# 150306_AriloTX_REV3_1_0_868MHZ_CORRECT_T.net
KiCad netlist of a schematic drawn in EAGLE
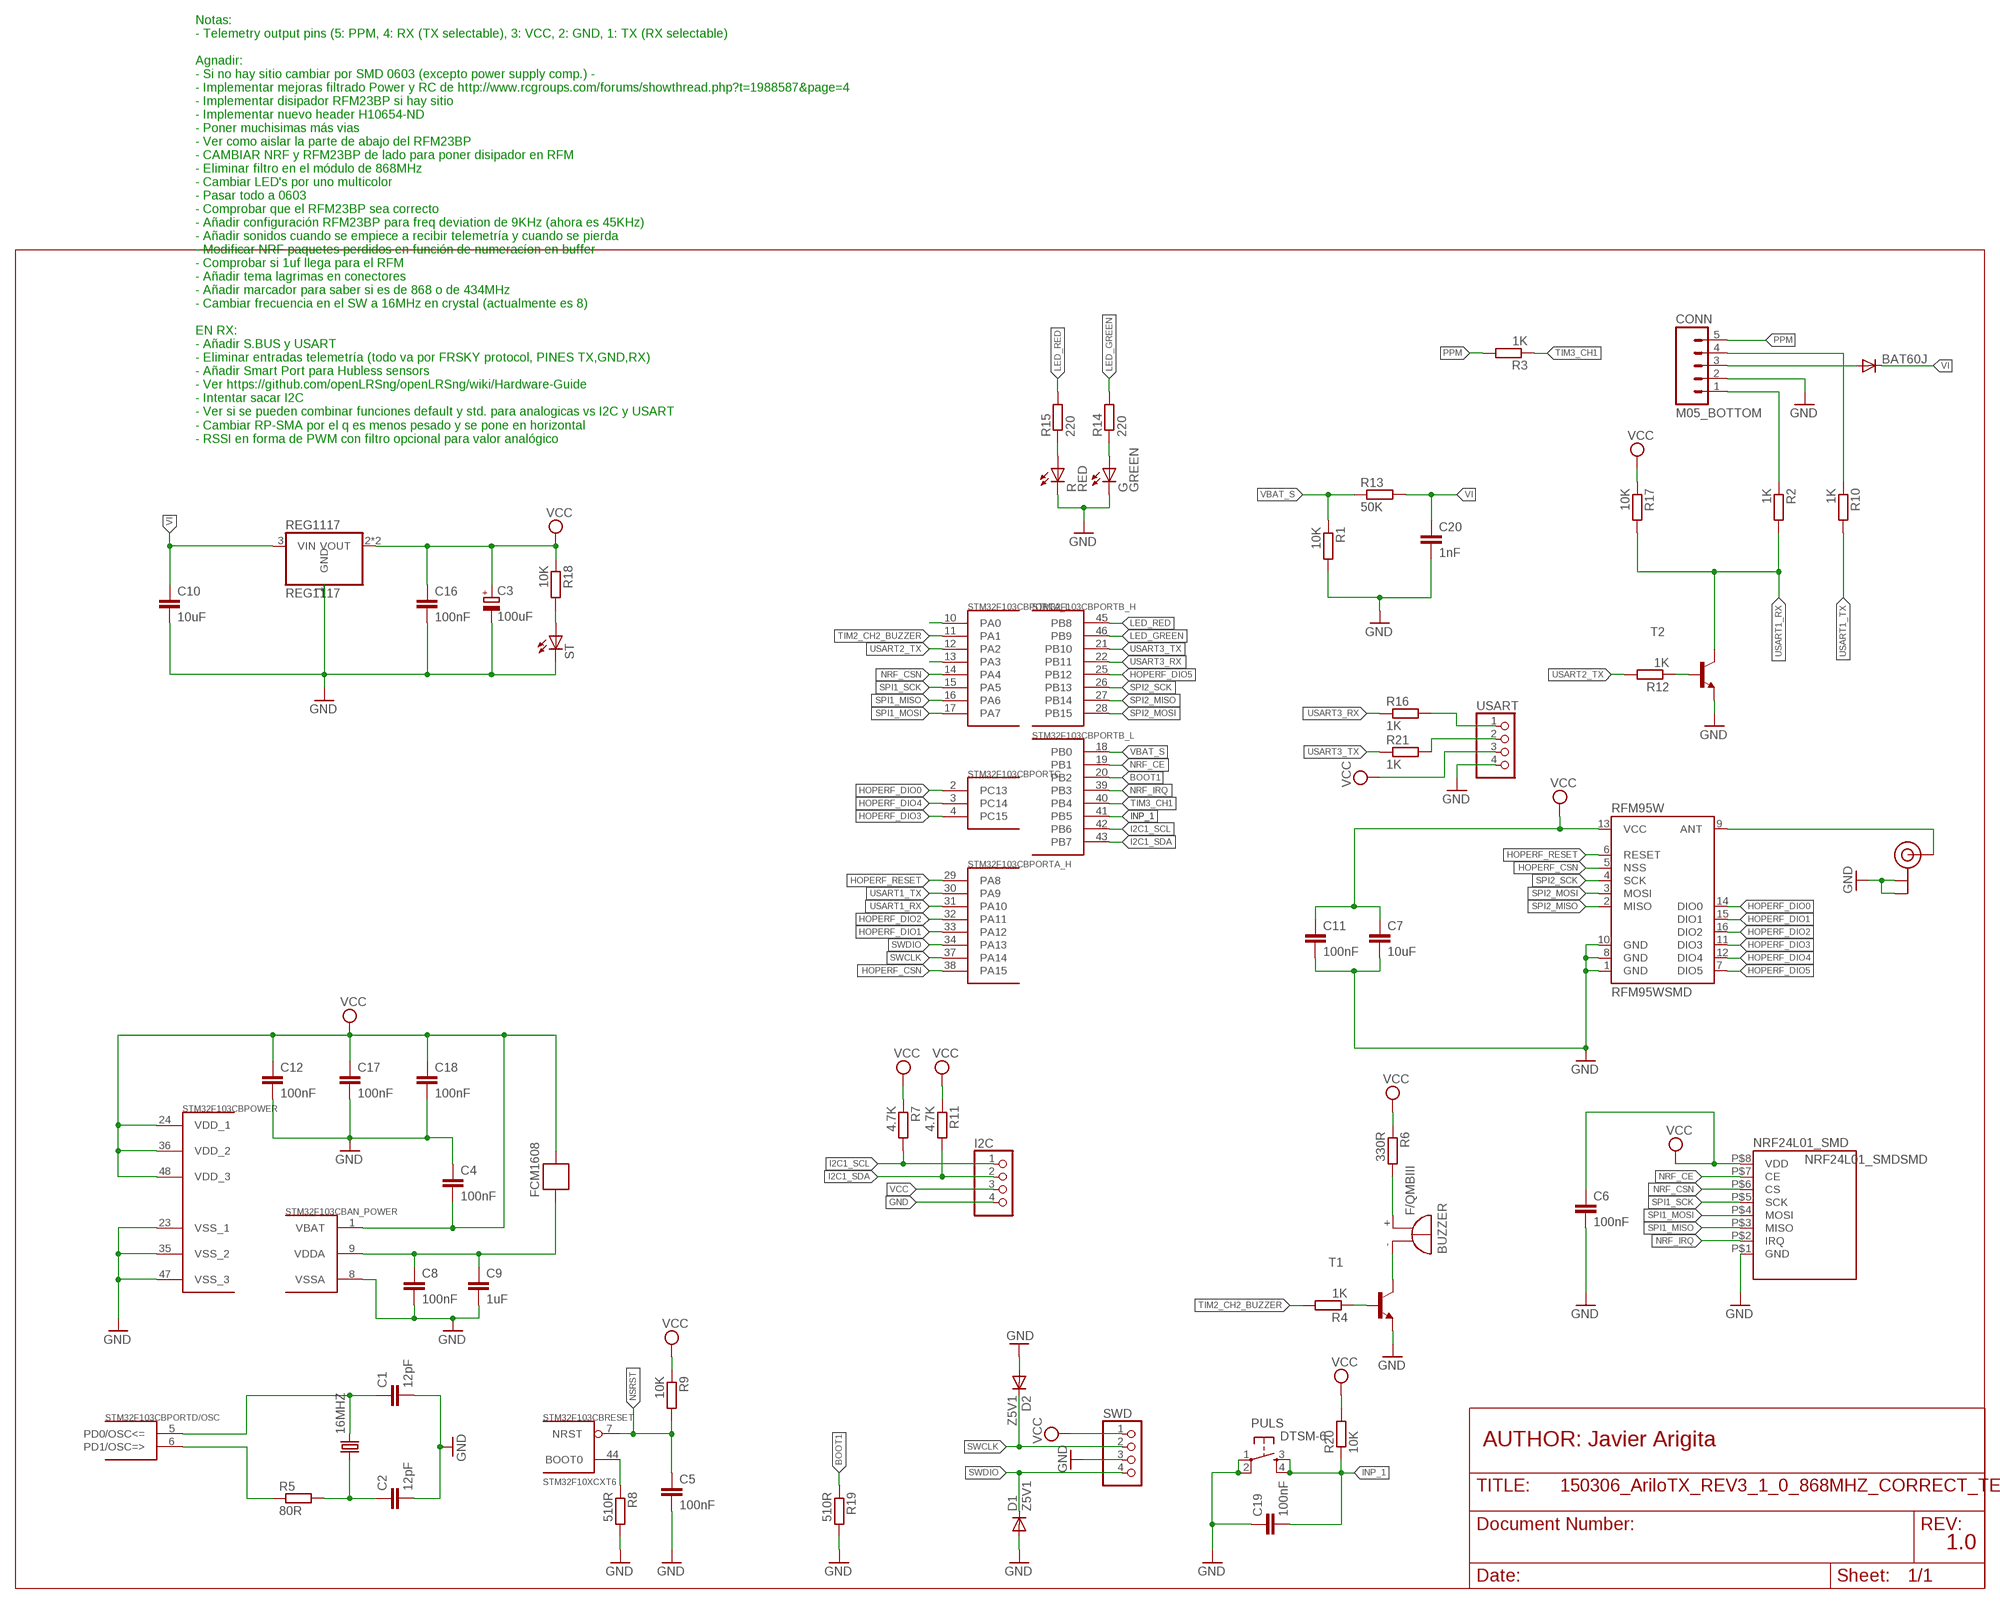
[diagram p0: schematic, sheet 1]

(export (version "E")
  (design (tool "Eeschema 10.0.6"))
  (components
    (comp (ref "16MHZ")
      (value "CRYSTAL5X3")
      (footprint "eagle-import:CRYSTAL-SMD-5X3")
      (libsource (lib "eagle-import") (part "CRYSTAL5X3"))
    )
    (comp (ref "BAT60J")
      (value "DIODE-SOD323-R")
      (footprint "eagle-import:SOD323-R")
      (libsource (lib "eagle-import") (part "DIODE-SOD323-R"))
    )
    (comp (ref "BUZZER")
      (value "F/QMBIII")
      (footprint "eagle-import:F_QMBIII")
      (libsource (lib "eagle-import") (part "F/QMBIII"))
    )
    (comp (ref "C1")
      (value "12pF")
      (footprint "eagle-import:C0603")
      (libsource (lib "eagle-import") (part "C-EUC0603"))
    )
    (comp (ref "C2")
      (value "12pF")
      (footprint "eagle-import:C0603")
      (libsource (lib "eagle-import") (part "C-EUC0603"))
    )
    (comp (ref "C3")
      (value "100uF")
      (footprint "eagle-import:SMC_B")
      (libsource (lib "eagle-import") (part "CPOL-EUSMCB"))
    )
    (comp (ref "C4")
      (value "100nF")
      (footprint "eagle-import:C0603")
      (libsource (lib "eagle-import") (part "C-EUC0603"))
    )
    (comp (ref "C5")
      (value "100nF")
      (footprint "eagle-import:C0603")
      (libsource (lib "eagle-import") (part "C-EUC0603"))
    )
    (comp (ref "C6")
      (value "100nF")
      (footprint "eagle-import:C0603")
      (libsource (lib "eagle-import") (part "C-EUC0603"))
    )
    (comp (ref "C7")
      (value "10uF")
      (footprint "eagle-import:C3216")
      (libsource (lib "eagle-import") (part "resistor_C-EUC3216"))
    )
    (comp (ref "C8")
      (value "100nF")
      (footprint "eagle-import:C0603")
      (libsource (lib "eagle-import") (part "C-EUC0603"))
    )
    (comp (ref "C9")
      (value "1uF")
      (footprint "eagle-import:C0603")
      (libsource (lib "eagle-import") (part "C-EUC0603"))
    )
    (comp (ref "C10")
      (value "10uF")
      (footprint "eagle-import:C3216")
      (libsource (lib "eagle-import") (part "resistor_C-EUC3216"))
    )
    (comp (ref "C11")
      (value "100nF")
      (footprint "eagle-import:C0603")
      (libsource (lib "eagle-import") (part "C-EUC0603"))
    )
    (comp (ref "C12")
      (value "100nF")
      (footprint "eagle-import:C0603")
      (libsource (lib "eagle-import") (part "C-EUC0603"))
    )
    (comp (ref "C16")
      (value "100nF")
      (footprint "eagle-import:C0603")
      (libsource (lib "eagle-import") (part "C-EUC0603"))
    )
    (comp (ref "C17")
      (value "100nF")
      (footprint "eagle-import:C0603")
      (libsource (lib "eagle-import") (part "C-EUC0603"))
    )
    (comp (ref "C18")
      (value "100nF")
      (footprint "eagle-import:C0603")
      (libsource (lib "eagle-import") (part "C-EUC0603"))
    )
    (comp (ref "C19")
      (value "100nF")
      (footprint "eagle-import:C0603")
      (libsource (lib "eagle-import") (part "C-EUC0603"))
    )
    (comp (ref "C20")
      (value "1nF")
      (footprint "eagle-import:C0603")
      (libsource (lib "eagle-import") (part "C-EUC0603"))
    )
    (comp (ref "CONN")
      (value "M05_BOTTOM")
      (footprint "eagle-import:M05_BOTTOM")
      (libsource (lib "eagle-import") (part "M05_BOTTOM"))
    )
    (comp (ref "D1")
      (value "Z5V1")
      (footprint "eagle-import:SOD323-R")
      (libsource (lib "eagle-import") (part "DIODE-SOD323-R"))
    )
    (comp (ref "D2")
      (value "Z5V1")
      (footprint "eagle-import:SOD323-R")
      (libsource (lib "eagle-import") (part "DIODE-SOD323-R"))
    )
    (comp (ref "FCM1608")
      (value "FERRITE-BEAD")
      (footprint "eagle-import:R0603")
      (libsource (lib "eagle-import") (part "FERRITE-BEAD"))
    )
    (comp (ref "G")
      (value "GREEN")
      (footprint "eagle-import:CHIP-LED0603")
      (libsource (lib "eagle-import") (part "LEDCHIP-LED0603"))
    )
    (comp (ref "I2C")
      (value "PINHD-1X4")
      (footprint "eagle-import:1X04")
      (libsource (lib "eagle-import") (part "PINHD-1X4"))
    )
    (comp (ref "NRF24L01_SMD")
      (value "NRF24L01_SMDSMD")
      (footprint "eagle-import:NRF24L01_SMD")
      (libsource (lib "eagle-import") (part "NRF24L01_SMDSMD"))
    )
    (comp (ref "PULS")
      (value "DTSM-6")
      (footprint "eagle-import:DTSM-6")
      (libsource (lib "eagle-import") (part "DTSM-6"))
    )
    (comp (ref "R")
      (value "RED")
      (footprint "eagle-import:CHIP-LED0603")
      (libsource (lib "eagle-import") (part "LEDCHIP-LED0603"))
    )
    (comp (ref "R1")
      (value "10K")
      (footprint "eagle-import:R0603")
      (libsource (lib "eagle-import") (part "R-EU_R0603"))
    )
    (comp (ref "R2")
      (value "1K")
      (footprint "eagle-import:R0603")
      (libsource (lib "eagle-import") (part "R-EU_R0603"))
    )
    (comp (ref "R3")
      (value "1K")
      (footprint "eagle-import:R0603")
      (libsource (lib "eagle-import") (part "R-EU_R0603"))
    )
    (comp (ref "R4")
      (value "1K")
      (footprint "eagle-import:R0603")
      (libsource (lib "eagle-import") (part "R-EU_R0603"))
    )
    (comp (ref "R5")
      (value "80R")
      (footprint "eagle-import:R0603")
      (libsource (lib "eagle-import") (part "R-EU_R0603"))
    )
    (comp (ref "R6")
      (value "330R")
      (footprint "eagle-import:R0603")
      (libsource (lib "eagle-import") (part "R-EU_R0603"))
    )
    (comp (ref "R7")
      (value "4.7K")
      (footprint "eagle-import:R0603")
      (libsource (lib "eagle-import") (part "R-EU_R0603"))
    )
    (comp (ref "R8")
      (value "510R")
      (footprint "eagle-import:R0603")
      (libsource (lib "eagle-import") (part "R-EU_R0603"))
    )
    (comp (ref "R9")
      (value "10K")
      (footprint "eagle-import:R0603")
      (libsource (lib "eagle-import") (part "R-EU_R0603"))
    )
    (comp (ref "R10")
      (value "1K")
      (footprint "eagle-import:R0603")
      (libsource (lib "eagle-import") (part "R-EU_R0603"))
    )
    (comp (ref "R11")
      (value "4.7K")
      (footprint "eagle-import:R0603")
      (libsource (lib "eagle-import") (part "R-EU_R0603"))
    )
    (comp (ref "R12")
      (value "1K")
      (footprint "eagle-import:R0603")
      (libsource (lib "eagle-import") (part "R-EU_R0603"))
    )
    (comp (ref "R13")
      (value "50K")
      (footprint "eagle-import:R0603")
      (libsource (lib "eagle-import") (part "R-EU_R0603"))
    )
    (comp (ref "R14")
      (value "220")
      (footprint "eagle-import:R0603")
      (libsource (lib "eagle-import") (part "R-EU_R0603"))
    )
    (comp (ref "R15")
      (value "220")
      (footprint "eagle-import:R0603")
      (libsource (lib "eagle-import") (part "R-EU_R0603"))
    )
    (comp (ref "R16")
      (value "1K")
      (footprint "eagle-import:R0603")
      (libsource (lib "eagle-import") (part "R-EU_R0603"))
    )
    (comp (ref "R17")
      (value "10K")
      (footprint "eagle-import:R0603")
      (libsource (lib "eagle-import") (part "R-EU_R0603"))
    )
    (comp (ref "R18")
      (value "10K")
      (footprint "eagle-import:R0603")
      (libsource (lib "eagle-import") (part "R-EU_R0603"))
    )
    (comp (ref "R19")
      (value "510R")
      (footprint "eagle-import:R0603")
      (libsource (lib "eagle-import") (part "R-EU_R0603"))
    )
    (comp (ref "R20")
      (value "10K")
      (footprint "eagle-import:R0603")
      (libsource (lib "eagle-import") (part "R-EU_R0603"))
    )
    (comp (ref "R21")
      (value "1K")
      (footprint "eagle-import:R0603")
      (libsource (lib "eagle-import") (part "R-EU_R0603"))
    )
    (comp (ref "REG1117")
      (value "REG1117")
      (footprint "eagle-import:SOT223")
      (libsource (lib "eagle-import") (part "REG1117"))
    )
    (comp (ref "RFM95W")
      (value "RFM95WSMD")
      (footprint "eagle-import:MISIEK_RFM95W_SMD")
      (libsource (lib "eagle-import") (part "MISIEK_RFM95WSMD"))
    )
    (comp (ref "ST")
      (value "LEDCHIP-LED0603")
      (footprint "eagle-import:CHIP-LED0603")
      (libsource (lib "eagle-import") (part "LEDCHIP-LED0603"))
    )
    (comp (ref "STM32F103CB")
      (value "STM32F10XCXT6")
      (footprint "eagle-import:TQFP48")
      (libsource (lib "eagle-import") (part "STM32F10XCXT6"))
    )
    (comp (ref "SWD")
      (value "PINHD-1X4")
      (footprint "eagle-import:1X04")
      (libsource (lib "eagle-import") (part "PINHD-1X4"))
    )
    (comp (ref "T1")
      (value "BC848-NPN-SOT23-BEC")
      (footprint "eagle-import:SOT23-BEC")
      (libsource (lib "eagle-import") (part "-NPN-SOT23-BECBC848"))
    )
    (comp (ref "T2")
      (value "BC848-NPN-SOT23-BEC")
      (footprint "eagle-import:SOT23-BEC")
      (libsource (lib "eagle-import") (part "-NPN-SOT23-BECBC848"))
    )
    (comp (ref "U.FL")
      (value "U.FL")
      (footprint "eagle-import:U.FL")
      (libsource (lib "eagle-import") (part "U.FL"))
    )
    (comp (ref "USART")
      (value "PINHD-1X4")
      (footprint "eagle-import:1X04")
      (libsource (lib "eagle-import") (part "PINHD-1X4"))
    )
  )
  (nets
    (net (code "1") (name "BOOT1") (class "Default")
      (node (ref "R19") (pin "1") (pinfunction "1_1") (pintype "passive"))
      (node (ref "STM32F103CB") (pin "20") (pinfunction "PB2_20") (pintype "bidirectional"))
    )
    (net (code "2") (name "GND") (class "Default")
      (node (ref "C1") (pin "2") (pinfunction "2_2") (pintype "passive"))
      (node (ref "C10") (pin "2") (pinfunction "2_2") (pintype "passive"))
      (node (ref "C11") (pin "2") (pinfunction "2_2") (pintype "passive"))
      (node (ref "C12") (pin "2") (pinfunction "2_2") (pintype "passive"))
      (node (ref "C16") (pin "2") (pinfunction "2_2") (pintype "passive"))
      (node (ref "C17") (pin "2") (pinfunction "2_2") (pintype "passive"))
      (node (ref "C18") (pin "2") (pinfunction "2_2") (pintype "passive"))
      (node (ref "C19") (pin "1") (pinfunction "1_1") (pintype "passive"))
      (node (ref "C2") (pin "2") (pinfunction "2_2") (pintype "passive"))
      (node (ref "C20") (pin "2") (pinfunction "2_2") (pintype "passive"))
      (node (ref "C3") (pin "-") (pinfunction "-_-") (pintype "passive"))
      (node (ref "C4") (pin "1") (pinfunction "1_1") (pintype "passive"))
      (node (ref "C5") (pin "2") (pinfunction "2_2") (pintype "passive"))
      (node (ref "C6") (pin "2") (pinfunction "2_2") (pintype "passive"))
      (node (ref "C7") (pin "2") (pinfunction "2_2") (pintype "passive"))
      (node (ref "C8") (pin "2") (pinfunction "2_2") (pintype "passive"))
      (node (ref "C9") (pin "2") (pinfunction "2_2") (pintype "passive"))
      (node (ref "CONN") (pin "2") (pinfunction "2_2") (pintype "passive"))
      (node (ref "D1") (pin "A") (pinfunction "A_A") (pintype "passive"))
      (node (ref "D2") (pin "A") (pinfunction "A_A") (pintype "passive"))
      (node (ref "G") (pin "C") (pinfunction "C_C") (pintype "passive"))
      (node (ref "I2C") (pin "4") (pinfunction "4_4") (pintype "passive"))
      (node (ref "NRF24L01_SMD") (pin "P$1") (pinfunction "GND_P$1") (pintype "power_in"))
      (node (ref "PULS") (pin "1") (pinfunction "1_1") (pintype "passive"))
      (node (ref "PULS") (pin "2") (pinfunction "2_2") (pintype "passive"))
      (node (ref "R") (pin "C") (pinfunction "C_C") (pintype "passive"))
      (node (ref "R1") (pin "2") (pinfunction "2_2") (pintype "passive"))
      (node (ref "R19") (pin "2") (pinfunction "2_2") (pintype "passive"))
      (node (ref "R8") (pin "2") (pinfunction "2_2") (pintype "passive"))
      (node (ref "REG1117") (pin "1") (pinfunction "GND_1") (pintype "power_in"))
      (node (ref "RFM95W") (pin "1") (pinfunction "GND_1") (pintype "power_in"))
      (node (ref "RFM95W") (pin "10") (pinfunction "GND_10") (pintype "power_in"))
      (node (ref "RFM95W") (pin "8") (pinfunction "GND_8") (pintype "power_in"))
      (node (ref "ST") (pin "C") (pinfunction "C_C") (pintype "passive"))
      (node (ref "STM32F103CB") (pin "23") (pinfunction "VSS_1_23") (pintype "power_in"))
      (node (ref "STM32F103CB") (pin "35") (pinfunction "VSS_2_35") (pintype "power_in"))
      (node (ref "STM32F103CB") (pin "47") (pinfunction "VSS_3_47") (pintype "power_in"))
      (node (ref "STM32F103CB") (pin "8") (pinfunction "VSSA_8") (pintype "power_in"))
      (node (ref "SWD") (pin "3") (pinfunction "3_3") (pintype "passive"))
      (node (ref "T1") (pin "E") (pinfunction "E_E") (pintype "passive"))
      (node (ref "T2") (pin "E") (pinfunction "E_E") (pintype "passive"))
      (node (ref "U.FL") (pin "P$1") (pinfunction "GND_P$1") (pintype "bidirectional"))
      (node (ref "U.FL") (pin "P$2") (pinfunction "GND_P$2") (pintype "bidirectional"))
      (node (ref "USART") (pin "4") (pinfunction "4_4") (pintype "passive"))
    )
    (net (code "3") (name "HOPERF_CSN") (class "Default")
      (node (ref "RFM95W") (pin "5") (pinfunction "NSS_5") (pintype "input"))
      (node (ref "STM32F103CB") (pin "38") (pinfunction "PA15_38") (pintype "bidirectional"))
    )
    (net (code "4") (name "HOPERF_DIO0") (class "Default")
      (node (ref "RFM95W") (pin "14") (pinfunction "DIO0_14") (pintype "input"))
      (node (ref "STM32F103CB") (pin "2") (pinfunction "PC13_2") (pintype "bidirectional"))
    )
    (net (code "5") (name "HOPERF_DIO1") (class "Default")
      (node (ref "RFM95W") (pin "15") (pinfunction "DIO1_15") (pintype "input"))
      (node (ref "STM32F103CB") (pin "33") (pinfunction "PA12_33") (pintype "bidirectional"))
    )
    (net (code "6") (name "HOPERF_DIO2") (class "Default")
      (node (ref "RFM95W") (pin "16") (pinfunction "DIO2_16") (pintype "input"))
      (node (ref "STM32F103CB") (pin "32") (pinfunction "PA11_32") (pintype "bidirectional"))
    )
    (net (code "7") (name "HOPERF_DIO3") (class "Default")
      (node (ref "RFM95W") (pin "11") (pinfunction "DIO3_11") (pintype "bidirectional"))
      (node (ref "STM32F103CB") (pin "4") (pinfunction "PC15_4") (pintype "bidirectional"))
    )
    (net (code "8") (name "HOPERF_DIO4") (class "Default")
      (node (ref "RFM95W") (pin "12") (pinfunction "DIO4_12") (pintype "bidirectional"))
      (node (ref "STM32F103CB") (pin "3") (pinfunction "PC14_3") (pintype "bidirectional"))
    )
    (net (code "9") (name "HOPERF_DIO5") (class "Default")
      (node (ref "RFM95W") (pin "7") (pinfunction "DIO5_7") (pintype "bidirectional"))
      (node (ref "STM32F103CB") (pin "25") (pinfunction "PB12_25") (pintype "bidirectional"))
    )
    (net (code "10") (name "HOPERF_RESET") (class "Default")
      (node (ref "RFM95W") (pin "6") (pinfunction "RESET_6") (pintype "output"))
      (node (ref "STM32F103CB") (pin "29") (pinfunction "PA8_29") (pintype "bidirectional"))
    )
    (net (code "11") (name "I2C1_SCL") (class "Default")
      (node (ref "I2C") (pin "1") (pinfunction "1_1") (pintype "passive"))
      (node (ref "R7") (pin "2") (pinfunction "2_2") (pintype "passive"))
      (node (ref "STM32F103CB") (pin "42") (pinfunction "PB6_42") (pintype "bidirectional"))
    )
    (net (code "12") (name "I2C1_SDA") (class "Default")
      (node (ref "I2C") (pin "2") (pinfunction "2_2") (pintype "passive"))
      (node (ref "R11") (pin "2") (pinfunction "2_2") (pintype "passive"))
      (node (ref "STM32F103CB") (pin "43") (pinfunction "PB7_43") (pintype "bidirectional"))
    )
    (net (code "13") (name "INP_1") (class "Default")
      (node (ref "C19") (pin "2") (pinfunction "2_2") (pintype "passive"))
      (node (ref "PULS") (pin "3") (pinfunction "3_3") (pintype "passive"))
      (node (ref "PULS") (pin "4") (pinfunction "4_4") (pintype "passive"))
      (node (ref "R20") (pin "1") (pinfunction "1_1") (pintype "passive"))
      (node (ref "STM32F103CB") (pin "41") (pinfunction "PB5_41") (pintype "bidirectional"))
    )
    (net (code "14") (name "LED_GREEN") (class "Default")
      (node (ref "R14") (pin "2") (pinfunction "2_2") (pintype "passive"))
      (node (ref "STM32F103CB") (pin "46") (pinfunction "PB9_46") (pintype "bidirectional"))
    )
    (net (code "15") (name "LED_RED") (class "Default")
      (node (ref "R15") (pin "2") (pinfunction "2_2") (pintype "passive"))
      (node (ref "STM32F103CB") (pin "45") (pinfunction "PB8_45") (pintype "bidirectional"))
    )
    (net (code "16") (name "NRF_CE") (class "Default")
      (node (ref "NRF24L01_SMD") (pin "P$7") (pinfunction "CE_P$7") (pintype "input"))
      (node (ref "STM32F103CB") (pin "19") (pinfunction "PB1_19") (pintype "bidirectional"))
    )
    (net (code "17") (name "NRF_CSN") (class "Default")
      (node (ref "NRF24L01_SMD") (pin "P$6") (pinfunction "CS_P$6") (pintype "input"))
      (node (ref "STM32F103CB") (pin "14") (pinfunction "PA4_14") (pintype "bidirectional"))
    )
    (net (code "18") (name "NRF_IRQ") (class "Default")
      (node (ref "NRF24L01_SMD") (pin "P$2") (pinfunction "IRQ_P$2") (pintype "output"))
      (node (ref "STM32F103CB") (pin "39") (pinfunction "PB3_39") (pintype "bidirectional"))
    )
    (net (code "19") (name "NSRST") (class "Default")
      (node (ref "C5") (pin "1") (pinfunction "1_1") (pintype "passive"))
      (node (ref "R9") (pin "2") (pinfunction "2_2") (pintype "passive"))
      (node (ref "STM32F103CB") (pin "7") (pinfunction "NRST_7") (pintype "input"))
    )
    (net (code "20") (name "Net-(16MHZ-2)") (class "Default")
      (node (ref "16MHZ") (pin "3") (pinfunction "2_3") (pintype "passive"))
      (node (ref "C1") (pin "1") (pinfunction "1_1") (pintype "passive"))
      (node (ref "STM32F103CB") (pin "5") (pinfunction "PD0/OSC<=_5") (pintype "bidirectional"))
    )
    (net (code "21") (name "Net-(16MHZ-Pad1)") (class "Default")
      (node (ref "16MHZ") (pin "1") (pinfunction "1_1") (pintype "passive"))
      (node (ref "C2") (pin "1") (pinfunction "1_1") (pintype "passive"))
      (node (ref "R5") (pin "2") (pinfunction "2_2") (pintype "passive"))
    )
    (net (code "22") (name "Net-(BAT60J-PadA)") (class "Default")
      (node (ref "BAT60J") (pin "A") (pinfunction "A_A") (pintype "passive"))
      (node (ref "CONN") (pin "3") (pinfunction "3_3") (pintype "passive"))
    )
    (net (code "23") (name "Net-(BUZZER-+)") (class "Default")
      (node (ref "BUZZER") (pin "-") (pinfunction "+_-") (pintype "passive"))
      (node (ref "T1") (pin "C") (pinfunction "C_C") (pintype "passive"))
    )
    (net (code "24") (name "Net-(BUZZER--)") (class "Default")
      (node (ref "BUZZER") (pin "+") (pinfunction "-_+") (pintype "passive"))
      (node (ref "R6") (pin "2") (pinfunction "2_2") (pintype "passive"))
    )
    (net (code "25") (name "Net-(CONN-Pad1)") (class "Default")
      (node (ref "CONN") (pin "1") (pinfunction "1_1") (pintype "passive"))
      (node (ref "R2") (pin "1") (pinfunction "1_1") (pintype "passive"))
    )
    (net (code "26") (name "Net-(CONN-Pad4)") (class "Default")
      (node (ref "CONN") (pin "4") (pinfunction "4_4") (pintype "passive"))
      (node (ref "R10") (pin "1") (pinfunction "1_1") (pintype "passive"))
    )
    (net (code "27") (name "Net-(FCM1608-P$2)") (class "Default")
      (node (ref "C8") (pin "1") (pinfunction "1_1") (pintype "passive"))
      (node (ref "C9") (pin "1") (pinfunction "1_1") (pintype "passive"))
      (node (ref "FCM1608") (pin "2") (pinfunction "P$2_2") (pintype "bidirectional"))
      (node (ref "STM32F103CB") (pin "9") (pinfunction "VDDA_9") (pintype "power_in"))
    )
    (net (code "28") (name "Net-(G-PadA)") (class "Default")
      (node (ref "G") (pin "A") (pinfunction "A_A") (pintype "passive"))
      (node (ref "R14") (pin "1") (pinfunction "1_1") (pintype "passive"))
    )
    (net (code "29") (name "Net-(R-PadA)") (class "Default")
      (node (ref "R") (pin "A") (pinfunction "A_A") (pintype "passive"))
      (node (ref "R15") (pin "1") (pinfunction "1_1") (pintype "passive"))
    )
    (net (code "30") (name "Net-(R4-Pad1)") (class "Default")
      (node (ref "R4") (pin "1") (pinfunction "1_1") (pintype "passive"))
      (node (ref "T1") (pin "B") (pinfunction "B_B") (pintype "passive"))
    )
    (net (code "31") (name "Net-(R12-Pad1)") (class "Default")
      (node (ref "R12") (pin "1") (pinfunction "1_1") (pintype "passive"))
      (node (ref "T2") (pin "B") (pinfunction "B_B") (pintype "passive"))
    )
    (net (code "32") (name "Net-(R16-Pad2)") (class "Default")
      (node (ref "R16") (pin "2") (pinfunction "2_2") (pintype "passive"))
      (node (ref "USART") (pin "1") (pinfunction "1_1") (pintype "passive"))
    )
    (net (code "33") (name "Net-(R18-Pad2)") (class "Default")
      (node (ref "R18") (pin "2") (pinfunction "2_2") (pintype "passive"))
      (node (ref "ST") (pin "A") (pinfunction "A_A") (pintype "passive"))
    )
    (net (code "34") (name "Net-(R21-Pad2)") (class "Default")
      (node (ref "R21") (pin "2") (pinfunction "2_2") (pintype "passive"))
      (node (ref "USART") (pin "2") (pinfunction "2_2") (pintype "passive"))
    )
    (net (code "35") (name "Net-(RFM95W-ANT)") (class "Default")
      (node (ref "RFM95W") (pin "9") (pinfunction "ANT_9") (pintype "bidirectional"))
      (node (ref "U.FL") (pin "P$3") (pinfunction "SIGNAL_P$3") (pintype "bidirectional"))
    )
    (net (code "36") (name "Net-(STM32F103CBG-PD1{slash}OSC=>)") (class "Default")
      (node (ref "R5") (pin "1") (pinfunction "1_1") (pintype "passive"))
      (node (ref "STM32F103CB") (pin "6") (pinfunction "PD1/OSC=>_6") (pintype "bidirectional"))
    )
    (net (code "37") (name "Net-(STM32F103CBI-BOOT0)") (class "Default")
      (node (ref "R8") (pin "1") (pinfunction "1_1") (pintype "passive"))
      (node (ref "STM32F103CB") (pin "44") (pinfunction "BOOT0_44") (pintype "input"))
    )
    (net (code "38") (name "PPM") (class "Default")
      (node (ref "CONN") (pin "5") (pinfunction "5_5") (pintype "passive"))
      (node (ref "R3") (pin "2") (pinfunction "2_2") (pintype "passive"))
    )
    (net (code "39") (name "SPI1_MISO") (class "Default")
      (node (ref "NRF24L01_SMD") (pin "P$3") (pinfunction "MISO_P$3") (pintype "output"))
      (node (ref "STM32F103CB") (pin "16") (pinfunction "PA6_16") (pintype "bidirectional"))
    )
    (net (code "40") (name "SPI1_MOSI") (class "Default")
      (node (ref "NRF24L01_SMD") (pin "P$4") (pinfunction "MOSI_P$4") (pintype "input"))
      (node (ref "STM32F103CB") (pin "17") (pinfunction "PA7_17") (pintype "bidirectional"))
    )
    (net (code "41") (name "SPI1_SCK") (class "Default")
      (node (ref "NRF24L01_SMD") (pin "P$5") (pinfunction "SCK_P$5") (pintype "input"))
      (node (ref "STM32F103CB") (pin "15") (pinfunction "PA5_15") (pintype "bidirectional"))
    )
    (net (code "42") (name "SPI2_MISO") (class "Default")
      (node (ref "RFM95W") (pin "2") (pinfunction "MISO_2") (pintype "output"))
      (node (ref "STM32F103CB") (pin "27") (pinfunction "PB14_27") (pintype "bidirectional"))
    )
    (net (code "43") (name "SPI2_MOSI") (class "Default")
      (node (ref "RFM95W") (pin "3") (pinfunction "MOSI_3") (pintype "input"))
      (node (ref "STM32F103CB") (pin "28") (pinfunction "PB15_28") (pintype "bidirectional"))
    )
    (net (code "44") (name "SPI2_SCK") (class "Default")
      (node (ref "RFM95W") (pin "4") (pinfunction "SCK_4") (pintype "input"))
      (node (ref "STM32F103CB") (pin "26") (pinfunction "PB13_26") (pintype "bidirectional"))
    )
    (net (code "45") (name "SWCLK") (class "Default")
      (node (ref "D2") (pin "C") (pinfunction "C_C") (pintype "passive"))
      (node (ref "STM32F103CB") (pin "37") (pinfunction "PA14_37") (pintype "bidirectional"))
      (node (ref "SWD") (pin "2") (pinfunction "2_2") (pintype "passive"))
    )
    (net (code "46") (name "SWDIO") (class "Default")
      (node (ref "D1") (pin "C") (pinfunction "C_C") (pintype "passive"))
      (node (ref "STM32F103CB") (pin "34") (pinfunction "PA13_34") (pintype "bidirectional"))
      (node (ref "SWD") (pin "4") (pinfunction "4_4") (pintype "passive"))
    )
    (net (code "47") (name "TIM2_CH2_BUZZER") (class "Default")
      (node (ref "R4") (pin "2") (pinfunction "2_2") (pintype "passive"))
      (node (ref "STM32F103CB") (pin "11") (pinfunction "PA1_11") (pintype "bidirectional"))
    )
    (net (code "48") (name "TIM3_CH1") (class "Default")
      (node (ref "R3") (pin "1") (pinfunction "1_1") (pintype "passive"))
      (node (ref "STM32F103CB") (pin "40") (pinfunction "PB4_40") (pintype "bidirectional"))
    )
    (net (code "49") (name "USART1_RX") (class "Default")
      (node (ref "R17") (pin "2") (pinfunction "2_2") (pintype "passive"))
      (node (ref "R2") (pin "2") (pinfunction "2_2") (pintype "passive"))
      (node (ref "STM32F103CB") (pin "31") (pinfunction "PA10_31") (pintype "bidirectional"))
      (node (ref "T2") (pin "C") (pinfunction "C_C") (pintype "passive"))
    )
    (net (code "50") (name "USART1_TX") (class "Default")
      (node (ref "R10") (pin "2") (pinfunction "2_2") (pintype "passive"))
      (node (ref "STM32F103CB") (pin "30") (pinfunction "PA9_30") (pintype "bidirectional"))
    )
    (net (code "51") (name "USART2_TX") (class "Default")
      (node (ref "R12") (pin "2") (pinfunction "2_2") (pintype "passive"))
      (node (ref "STM32F103CB") (pin "12") (pinfunction "PA2_12") (pintype "bidirectional"))
    )
    (net (code "52") (name "USART3_RX") (class "Default")
      (node (ref "R16") (pin "1") (pinfunction "1_1") (pintype "passive"))
      (node (ref "STM32F103CB") (pin "22") (pinfunction "PB11_22") (pintype "bidirectional"))
    )
    (net (code "53") (name "USART3_TX") (class "Default")
      (node (ref "R21") (pin "1") (pinfunction "1_1") (pintype "passive"))
      (node (ref "STM32F103CB") (pin "21") (pinfunction "PB10_21") (pintype "bidirectional"))
    )
    (net (code "54") (name "VBAT_S") (class "Default")
      (node (ref "R1") (pin "1") (pinfunction "1_1") (pintype "passive"))
      (node (ref "R13") (pin "1") (pinfunction "1_1") (pintype "passive"))
      (node (ref "STM32F103CB") (pin "18") (pinfunction "PB0_18") (pintype "bidirectional"))
    )
    (net (code "55") (name "VCC") (class "Default")
      (node (ref "C11") (pin "1") (pinfunction "1_1") (pintype "passive"))
      (node (ref "C12") (pin "1") (pinfunction "1_1") (pintype "passive"))
      (node (ref "C16") (pin "1") (pinfunction "1_1") (pintype "passive"))
      (node (ref "C17") (pin "1") (pinfunction "1_1") (pintype "passive"))
      (node (ref "C18") (pin "1") (pinfunction "1_1") (pintype "passive"))
      (node (ref "C3") (pin "+") (pinfunction "+_+") (pintype "passive"))
      (node (ref "C4") (pin "2") (pinfunction "2_2") (pintype "passive"))
      (node (ref "C6") (pin "1") (pinfunction "1_1") (pintype "passive"))
      (node (ref "C7") (pin "1") (pinfunction "1_1") (pintype "passive"))
      (node (ref "FCM1608") (pin "1") (pinfunction "P$1_1") (pintype "bidirectional"))
      (node (ref "I2C") (pin "3") (pinfunction "3_3") (pintype "passive"))
      (node (ref "NRF24L01_SMD") (pin "P$8") (pinfunction "VDD_P$8") (pintype "bidirectional"))
      (node (ref "R11") (pin "1") (pinfunction "1_1") (pintype "passive"))
      (node (ref "R17") (pin "1") (pinfunction "1_1") (pintype "passive"))
      (node (ref "R18") (pin "1") (pinfunction "1_1") (pintype "passive"))
      (node (ref "R20") (pin "2") (pinfunction "2_2") (pintype "passive"))
      (node (ref "R6") (pin "1") (pinfunction "1_1") (pintype "passive"))
      (node (ref "R7") (pin "1") (pinfunction "1_1") (pintype "passive"))
      (node (ref "R9") (pin "1") (pinfunction "1_1") (pintype "passive"))
      (node (ref "REG1117") (pin "2") (pinfunction "VOUT_2") (pintype "power_in"))
      (node (ref "REG1117") (pin "4") (pinfunction "VOUT_4") (pintype "power_in"))
      (node (ref "RFM95W") (pin "13") (pinfunction "VCC_13") (pintype "bidirectional"))
      (node (ref "STM32F103CB") (pin "1") (pinfunction "VBAT_1") (pintype "power_in"))
      (node (ref "STM32F103CB") (pin "24") (pinfunction "VDD_1_24") (pintype "power_in"))
      (node (ref "STM32F103CB") (pin "36") (pinfunction "VDD_2_36") (pintype "power_in"))
      (node (ref "STM32F103CB") (pin "48") (pinfunction "VDD_3_48") (pintype "power_in"))
      (node (ref "SWD") (pin "1") (pinfunction "1_1") (pintype "passive"))
      (node (ref "USART") (pin "3") (pinfunction "3_3") (pintype "passive"))
    )
    (net (code "56") (name "VI") (class "Default")
      (node (ref "BAT60J") (pin "C") (pinfunction "C_C") (pintype "passive"))
      (node (ref "C10") (pin "1") (pinfunction "1_1") (pintype "passive"))
      (node (ref "C20") (pin "1") (pinfunction "1_1") (pintype "passive"))
      (node (ref "R13") (pin "2") (pinfunction "2_2") (pintype "passive"))
      (node (ref "REG1117") (pin "3") (pinfunction "VIN_3") (pintype "input"))
    )
    (net (code "57") (name "unconnected-(STM32F103CBC-PA0-Pad10)") (class "Default")
      (node (ref "STM32F103CB") (pin "10") (pinfunction "PA0_10") (pintype "bidirectional"))
    )
    (net (code "58") (name "unconnected-(STM32F103CBC-PA3-Pad13)") (class "Default")
      (node (ref "STM32F103CB") (pin "13") (pinfunction "PA3_13") (pintype "bidirectional"))
    )
  )
)
